# 05_USART.net
KiCad netlist of a schematic drawn in Altium Designer
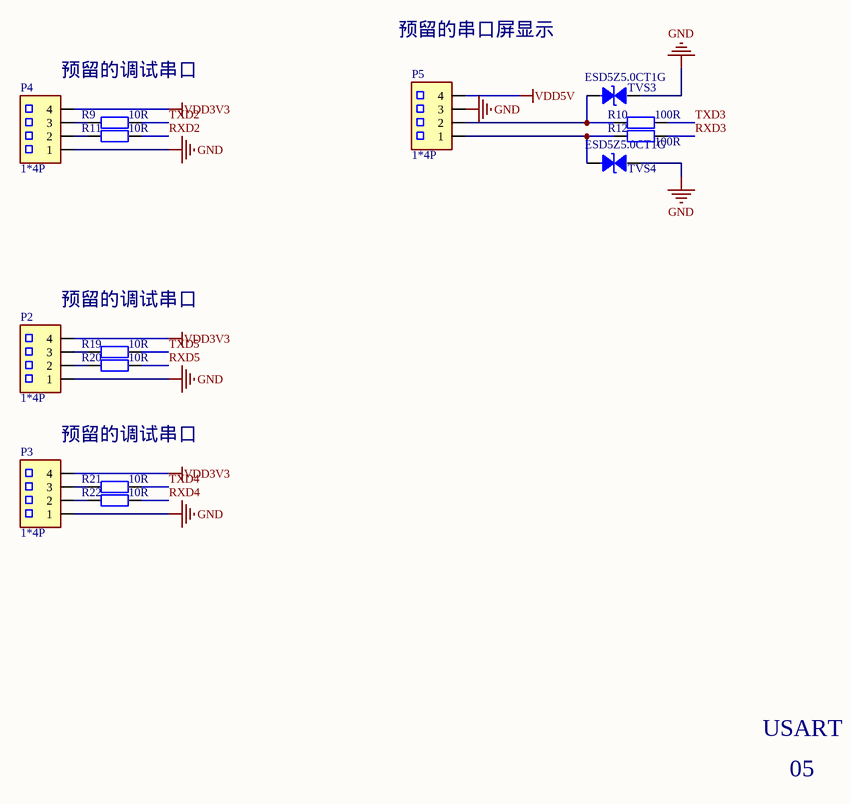
[diagram p0: 05_USART.SchDoc]

(export (version "E")
  (design (tool "Eeschema 10.0.6"))
  (components
    (comp (ref "P2") (value "1*4P") (footprint "4X2.54MMW") (libsource (lib "PARK-N5 V1.0") (part "HDR1*4")))
    (comp (ref "P3") (value "1*4P") (footprint "4X2.54MMW") (libsource (lib "PARK-N5 V1.0") (part "HDR1*4")))
    (comp (ref "P4") (value "1*4P") (footprint "4X2.54MMW") (libsource (lib "PARK-N5 V1.0") (part "HDR1*4")))
    (comp (ref "P5") (value "1*4P") (footprint "4X2.54MMW") (libsource (lib "PARK-N5 V1.0") (part "HDR1*4")))
    (comp (ref "R9")
      (value "10R")
      (footprint "SMD-0603")
      (description "贴片电阻 5%")
      (libsource (lib "XiaoyI") (part "RES2"))
    )
    (comp (ref "R10")
      (value "100R")
      (footprint "SMD-0603")
      (description "贴片电阻 5%")
      (libsource (lib "XiaoyI") (part "RES2"))
    )
    (comp (ref "R11")
      (value "10R")
      (footprint "SMD-0603")
      (description "贴片电阻 5%")
      (libsource (lib "XiaoyI") (part "RES2"))
    )
    (comp (ref "R12")
      (value "100R")
      (footprint "SMD-0603")
      (description "贴片电阻 5%")
      (libsource (lib "XiaoyI") (part "RES2"))
    )
    (comp (ref "R19")
      (value "10R")
      (footprint "SMD-0603")
      (description "贴片电阻 5%")
      (libsource (lib "XiaoyI") (part "RES2"))
    )
    (comp (ref "R20")
      (value "10R")
      (footprint "SMD-0603")
      (description "贴片电阻 5%")
      (libsource (lib "XiaoyI") (part "RES2"))
    )
    (comp (ref "R21")
      (value "10R")
      (footprint "SMD-0603")
      (description "贴片电阻 5%")
      (libsource (lib "XiaoyI") (part "RES2"))
    )
    (comp (ref "R22")
      (value "10R")
      (footprint "SMD-0603")
      (description "贴片电阻 5%")
      (libsource (lib "XiaoyI") (part "RES2"))
    )
    (comp (ref "TVS3")
      (value "ESD5Z5.0CT1G")
      (footprint "SOD-523")
      (description "TVS")
      (libsource (lib "XiaoyI") (part "TVS-1"))
    )
    (comp (ref "TVS4")
      (value "ESD5Z5.0CT1G")
      (footprint "SOD-523")
      (description "TVS")
      (libsource (lib "XiaoyI") (part "TVS-1"))
    )
  )
  (nets
    (net (code "1") (name "/RXD2") (class "Default")
      (node (ref "R11") (pin "2") (pinfunction "2_2") (pintype "passive"))
    )
    (net (code "2") (name "/RXD3") (class "Default")
      (node (ref "R12") (pin "2") (pinfunction "2_2") (pintype "passive"))
    )
    (net (code "3") (name "/RXD4") (class "Default")
      (node (ref "R22") (pin "2") (pinfunction "2_2") (pintype "passive"))
    )
    (net (code "4") (name "/RXD5") (class "Default")
      (node (ref "R20") (pin "2") (pinfunction "2_2") (pintype "passive"))
    )
    (net (code "5") (name "/TXD2") (class "Default")
      (node (ref "R9") (pin "2") (pinfunction "2_2") (pintype "passive"))
    )
    (net (code "6") (name "/TXD3") (class "Default")
      (node (ref "R10") (pin "2") (pinfunction "2_2") (pintype "passive"))
    )
    (net (code "7") (name "/TXD4") (class "Default")
      (node (ref "R21") (pin "2") (pinfunction "2_2") (pintype "passive"))
    )
    (net (code "8") (name "/TXD5") (class "Default")
      (node (ref "R19") (pin "2") (pinfunction "2_2") (pintype "passive"))
    )
    (net (code "9") (name "GND") (class "Default")
      (node (ref "P2") (pin "1") (pinfunction "1_1") (pintype "passive"))
      (node (ref "P3") (pin "1") (pinfunction "1_1") (pintype "passive"))
      (node (ref "P4") (pin "1") (pinfunction "1_1") (pintype "passive"))
      (node (ref "P5") (pin "3") (pinfunction "3_3") (pintype "passive"))
      (node (ref "TVS3") (pin "1") (pinfunction "A_1") (pintype "passive"))
      (node (ref "TVS4") (pin "1") (pinfunction "A_1") (pintype "passive"))
    )
    (net (code "10") (name "Net-(P2-Pad2)") (class "Default")
      (node (ref "P2") (pin "2") (pinfunction "2_2") (pintype "passive"))
      (node (ref "R20") (pin "1") (pinfunction "1_1") (pintype "passive"))
    )
    (net (code "11") (name "Net-(P2-Pad3)") (class "Default")
      (node (ref "P2") (pin "3") (pinfunction "3_3") (pintype "passive"))
      (node (ref "R19") (pin "1") (pinfunction "1_1") (pintype "passive"))
    )
    (net (code "12") (name "Net-(P3-Pad2)") (class "Default")
      (node (ref "P3") (pin "2") (pinfunction "2_2") (pintype "passive"))
      (node (ref "R22") (pin "1") (pinfunction "1_1") (pintype "passive"))
    )
    (net (code "13") (name "Net-(P3-Pad3)") (class "Default")
      (node (ref "P3") (pin "3") (pinfunction "3_3") (pintype "passive"))
      (node (ref "R21") (pin "1") (pinfunction "1_1") (pintype "passive"))
    )
    (net (code "14") (name "Net-(P4-Pad2)") (class "Default")
      (node (ref "P4") (pin "2") (pinfunction "2_2") (pintype "passive"))
      (node (ref "R11") (pin "1") (pinfunction "1_1") (pintype "passive"))
    )
    (net (code "15") (name "Net-(P4-Pad3)") (class "Default")
      (node (ref "P4") (pin "3") (pinfunction "3_3") (pintype "passive"))
      (node (ref "R9") (pin "1") (pinfunction "1_1") (pintype "passive"))
    )
    (net (code "16") (name "Net-(TVS3-B)") (class "Default")
      (node (ref "P5") (pin "2") (pinfunction "2_2") (pintype "passive"))
      (node (ref "R10") (pin "1") (pinfunction "1_1") (pintype "passive"))
      (node (ref "TVS3") (pin "2") (pinfunction "B_2") (pintype "passive"))
    )
    (net (code "17") (name "Net-(TVS4-B)") (class "Default")
      (node (ref "P5") (pin "1") (pinfunction "1_1") (pintype "passive"))
      (node (ref "R12") (pin "1") (pinfunction "1_1") (pintype "passive"))
      (node (ref "TVS4") (pin "2") (pinfunction "B_2") (pintype "passive"))
    )
    (net (code "18") (name "VDD3V3") (class "Default")
      (node (ref "P2") (pin "4") (pinfunction "4_4") (pintype "passive"))
      (node (ref "P3") (pin "4") (pinfunction "4_4") (pintype "passive"))
      (node (ref "P4") (pin "4") (pinfunction "4_4") (pintype "passive"))
    )
    (net (code "19") (name "VDD5V") (class "Default")
      (node (ref "P5") (pin "4") (pinfunction "4_4") (pintype "passive"))
    )
  )
)
